# Sheet1.net
KiCad netlist of a schematic drawn in Altium Designer
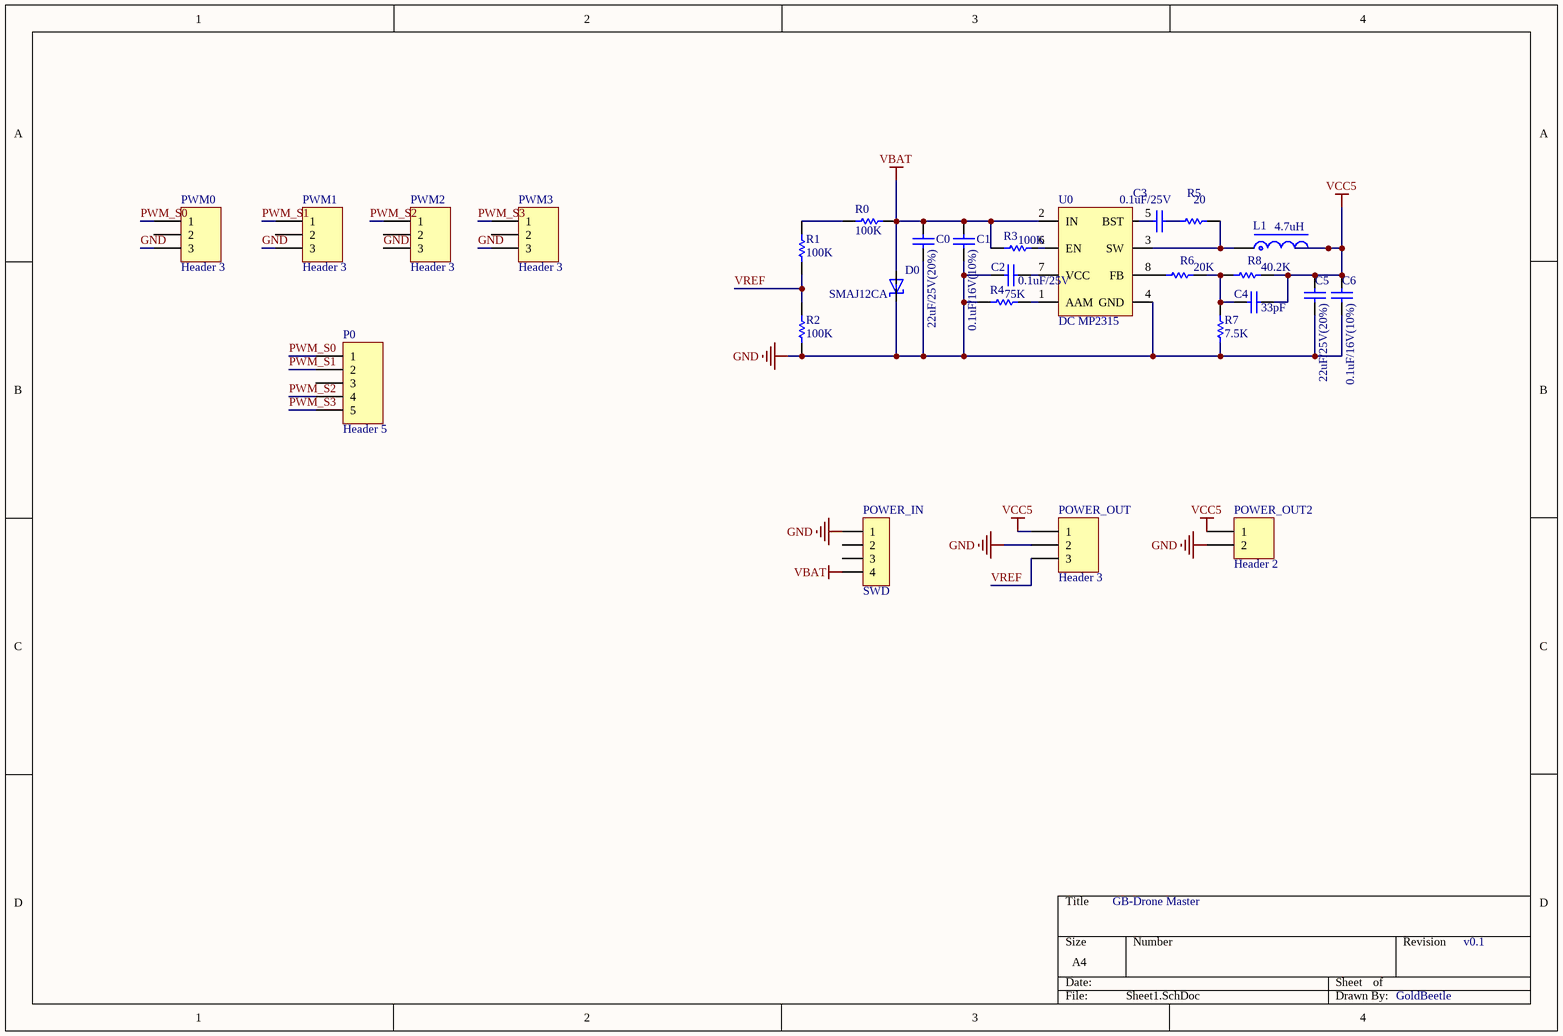
[diagram p0: Sheet1.SchDoc]

(export (version "E")
  (design (tool "Eeschema 10.0.6"))
  (components
    (comp (ref "C0")
      (value "22uF/25V(20%)")
      (footprint "C0805")
      (description "Capacitor")
      (fields (field (name "PUBLISHER") "Altium Limited"))
      (libsource (lib "Miscellaneous Devices") (part "Cap"))
    )
    (comp (ref "C1")
      (value "0.1uF/16V(10%)")
      (footprint "C0805")
      (description "Capacitor")
      (fields (field (name "PUBLISHER") "Altium Limited"))
      (libsource (lib "Miscellaneous Devices") (part "Cap"))
    )
    (comp (ref "C2")
      (value "0.1uF/25V")
      (footprint "C0805")
      (description "Capacitor")
      (fields (field (name "PUBLISHER") "Altium Limited"))
      (libsource (lib "Miscellaneous Devices") (part "Cap"))
    )
    (comp (ref "C3")
      (value "0.1uF/25V")
      (footprint "C0805")
      (description "Capacitor")
      (fields (field (name "PUBLISHER") "Altium Limited"))
      (libsource (lib "Miscellaneous Devices") (part "Cap"))
    )
    (comp (ref "C4")
      (value "33pF")
      (footprint "C0805")
      (description "Capacitor")
      (fields (field (name "PUBLISHER") "Altium Limited"))
      (libsource (lib "Miscellaneous Devices") (part "Cap"))
    )
    (comp (ref "C5")
      (value "22uF/25V(20%)")
      (footprint "C0805")
      (description "Capacitor")
      (fields (field (name "PUBLISHER") "Altium Limited"))
      (libsource (lib "Miscellaneous Devices") (part "Cap"))
    )
    (comp (ref "C6")
      (value "0.1uF/16V(10%)")
      (footprint "C0805")
      (description "Capacitor")
      (fields (field (name "PUBLISHER") "Altium Limited"))
      (libsource (lib "Miscellaneous Devices") (part "Cap"))
    )
    (comp (ref "D0")
      (value "SMAJ12CA")
      (footprint "DO-214AC")
      (description "19.9V Clamp 20.1A Ipp Tvs Diode Surface Mount SMAJ _DO-214AC_")
      (fields (field (name "MF") "Taiwan Semiconductor"))
      (libsource (lib "welkin_lib_v1.0") (part "SMAJ12CA"))
    )
    (comp (ref "L1")
      (value "4.7uH")
      (footprint "INDC6060X300")
      (description "NR功率电感")
      (fields (field (name "版权归属") "源创客"))
      (libsource (lib "welkin_lib_v1.0") (part "L-NR"))
    )
    (comp (ref "P0")
      (value "Header 5")
      (footprint "welkin_pcblib_v1.0:XH2.54-5P")
      (description "Header, 5-Pin")
      (fields (field (name "PUBLISHER") "Altium Limited"))
      (libsource (lib "Miscellaneous Connectors") (part "Header 5"))
    )
    (comp (ref "POWER_IN")
      (value "SWD")
      (footprint "welkin_pcblib_v1.0:XH2.54-4P")
      (description "4P接插件")
      (fields (field (name "版权归属") "源创客"))
      (libsource (lib "welkin_lib_v1.0") (part "Header 4"))
    )
    (comp (ref "POWER_OUT")
      (value "Header 3")
      (footprint "welkin_pcblib_v1.0:XH2.54-3P")
      (description "Header, 3-Pin")
      (fields (field (name "PUBLISHER") "Altium Limited"))
      (libsource (lib "Miscellaneous Connectors") (part "Header 3"))
    )
    (comp (ref "POWER_OUT2")
      (value "Header 2")
      (footprint "welkin_pcblib_v1.0:XH2.54-2P")
      (description "Header, 2-Pin")
      (fields (field (name "PUBLISHER") "Altium Limited"))
      (libsource (lib "Miscellaneous Connectors") (part "Header 2"))
    )
    (comp (ref "PWM0")
      (value "Header 3")
      (footprint "welkin_pcblib_v1.0:XH2.54-3P")
      (description "Header, 3-Pin")
      (fields (field (name "PUBLISHER") "Altium Limited"))
      (libsource (lib "Miscellaneous Connectors") (part "Header 3"))
    )
    (comp (ref "PWM1")
      (value "Header 3")
      (footprint "welkin_pcblib_v1.0:XH2.54-3P")
      (description "Header, 3-Pin")
      (fields (field (name "PUBLISHER") "Altium Limited"))
      (libsource (lib "Miscellaneous Connectors") (part "Header 3"))
    )
    (comp (ref "PWM2")
      (value "Header 3")
      (footprint "welkin_pcblib_v1.0:XH2.54-3P")
      (description "Header, 3-Pin")
      (fields (field (name "PUBLISHER") "Altium Limited"))
      (libsource (lib "Miscellaneous Connectors") (part "Header 3"))
    )
    (comp (ref "PWM3")
      (value "Header 3")
      (footprint "welkin_pcblib_v1.0:XH2.54-3P")
      (description "Header, 3-Pin")
      (fields (field (name "PUBLISHER") "Altium Limited"))
      (libsource (lib "Miscellaneous Connectors") (part "Header 3"))
    )
    (comp (ref "R0")
      (value "100K")
      (footprint "C0805")
      (description "Resistor")
      (fields (field (name "PUBLISHER") "Altium Limited"))
      (libsource (lib "Miscellaneous Devices") (part "Res1"))
    )
    (comp (ref "R1")
      (value "100K")
      (footprint "C0805")
      (description "Resistor")
      (fields (field (name "PUBLISHER") "Altium Limited"))
      (libsource (lib "Miscellaneous Devices") (part "Res1"))
    )
    (comp (ref "R2")
      (value "100K")
      (footprint "C0805")
      (description "Resistor")
      (fields (field (name "PUBLISHER") "Altium Limited"))
      (libsource (lib "Miscellaneous Devices") (part "Res1"))
    )
    (comp (ref "R3")
      (value "100K")
      (footprint "C0805")
      (description "Resistor")
      (fields (field (name "PUBLISHER") "Altium Limited"))
      (libsource (lib "Miscellaneous Devices") (part "Res1"))
    )
    (comp (ref "R4")
      (value "75K")
      (footprint "C0805")
      (description "Resistor")
      (fields (field (name "PUBLISHER") "Altium Limited"))
      (libsource (lib "Miscellaneous Devices") (part "Res1"))
    )
    (comp (ref "R5")
      (value "20")
      (footprint "C0805")
      (description "Resistor")
      (fields (field (name "PUBLISHER") "Altium Limited"))
      (libsource (lib "Miscellaneous Devices") (part "Res1"))
    )
    (comp (ref "R6")
      (value "20K")
      (footprint "C0805")
      (description "Resistor")
      (fields (field (name "PUBLISHER") "Altium Limited"))
      (libsource (lib "Miscellaneous Devices") (part "Res1"))
    )
    (comp (ref "R7")
      (value "7.5K")
      (footprint "C0805")
      (description "Resistor")
      (fields (field (name "PUBLISHER") "Altium Limited"))
      (libsource (lib "Miscellaneous Devices") (part "Res1"))
    )
    (comp (ref "R8")
      (value "40.2K")
      (footprint "C0805")
      (description "Resistor")
      (fields (field (name "PUBLISHER") "Altium Limited"))
      (libsource (lib "Miscellaneous Devices") (part "Res1"))
    )
    (comp (ref "U0")
      (value "DC MP2315")
      (footprint "SOT23-8L")
      (description "DC降压芯片")
      (libsource (lib "welkin_lib_v1.0") (part "DC MP2315"))
    )
  )
  (nets
    (net (code "1") (name "/PWM_S0") (class "Default")
      (node (ref "P0") (pin "1") (pinfunction "1_1") (pintype "passive"))
      (node (ref "PWM0") (pin "1") (pinfunction "1_1") (pintype "passive"))
    )
    (net (code "2") (name "/PWM_S1") (class "Default")
      (node (ref "P0") (pin "2") (pinfunction "2_2") (pintype "passive"))
      (node (ref "PWM1") (pin "1") (pinfunction "1_1") (pintype "passive"))
    )
    (net (code "3") (name "/PWM_S2") (class "Default")
      (node (ref "P0") (pin "4") (pinfunction "4_4") (pintype "passive"))
      (node (ref "PWM2") (pin "1") (pinfunction "1_1") (pintype "passive"))
    )
    (net (code "4") (name "/PWM_S3") (class "Default")
      (node (ref "P0") (pin "5") (pinfunction "5_5") (pintype "passive"))
      (node (ref "PWM3") (pin "1") (pinfunction "1_1") (pintype "passive"))
    )
    (net (code "5") (name "/VREF") (class "Default")
      (node (ref "POWER_OUT") (pin "3") (pinfunction "3_3") (pintype "passive"))
      (node (ref "R1") (pin "2") (pinfunction "2_2") (pintype "passive"))
      (node (ref "R2") (pin "2") (pinfunction "2_2") (pintype "passive"))
    )
    (net (code "6") (name "GND") (class "Default")
      (node (ref "C0") (pin "1") (pinfunction "1_1") (pintype "passive"))
      (node (ref "C1") (pin "1") (pinfunction "1_1") (pintype "passive"))
      (node (ref "C2") (pin "1") (pinfunction "1_1") (pintype "passive"))
      (node (ref "C5") (pin "1") (pinfunction "1_1") (pintype "passive"))
      (node (ref "C6") (pin "1") (pinfunction "1_1") (pintype "passive"))
      (node (ref "D0") (pin "C") (pinfunction "C_C") (pintype "passive"))
      (node (ref "POWER_IN") (pin "1") (pinfunction "1_1") (pintype "passive"))
      (node (ref "POWER_OUT") (pin "2") (pinfunction "2_2") (pintype "passive"))
      (node (ref "POWER_OUT2") (pin "2") (pinfunction "2_2") (pintype "passive"))
      (node (ref "PWM0") (pin "3") (pinfunction "3_3") (pintype "passive"))
      (node (ref "PWM1") (pin "3") (pinfunction "3_3") (pintype "passive"))
      (node (ref "PWM2") (pin "3") (pinfunction "3_3") (pintype "passive"))
      (node (ref "PWM3") (pin "3") (pinfunction "3_3") (pintype "passive"))
      (node (ref "R2") (pin "1") (pinfunction "1_1") (pintype "passive"))
      (node (ref "R4") (pin "1") (pinfunction "1_1") (pintype "passive"))
      (node (ref "R7") (pin "2") (pinfunction "2_2") (pintype "passive"))
      (node (ref "U0") (pin "4") (pinfunction "GND_4") (pintype "passive"))
    )
    (net (code "7") (name "Net-(C3-Pad2)") (class "Default")
      (node (ref "C3") (pin "2") (pinfunction "2_2") (pintype "passive"))
      (node (ref "R5") (pin "1") (pinfunction "1_1") (pintype "passive"))
    )
    (net (code "8") (name "Net-(C4-Pad1)") (class "Default")
      (node (ref "C4") (pin "1") (pinfunction "1_1") (pintype "passive"))
      (node (ref "R6") (pin "2") (pinfunction "2_2") (pintype "passive"))
      (node (ref "R7") (pin "1") (pinfunction "1_1") (pintype "passive"))
      (node (ref "R8") (pin "1") (pinfunction "1_1") (pintype "passive"))
    )
    (net (code "9") (name "Net-(R0-Pad2)") (class "Default")
      (node (ref "R0") (pin "2") (pinfunction "2_2") (pintype "passive"))
      (node (ref "R1") (pin "1") (pinfunction "1_1") (pintype "passive"))
    )
    (net (code "10") (name "Net-(U0-AAM)") (class "Default")
      (node (ref "R4") (pin "2") (pinfunction "2_2") (pintype "passive"))
      (node (ref "U0") (pin "1") (pinfunction "AAM_1") (pintype "passive"))
    )
    (net (code "11") (name "Net-(U0-BST)") (class "Default")
      (node (ref "C3") (pin "1") (pinfunction "1_1") (pintype "passive"))
      (node (ref "U0") (pin "5") (pinfunction "BST_5") (pintype "passive"))
    )
    (net (code "12") (name "Net-(U0-EN)") (class "Default")
      (node (ref "R3") (pin "2") (pinfunction "2_2") (pintype "passive"))
      (node (ref "U0") (pin "6") (pinfunction "EN_6") (pintype "passive"))
    )
    (net (code "13") (name "Net-(U0-FB)") (class "Default")
      (node (ref "R6") (pin "1") (pinfunction "1_1") (pintype "passive"))
      (node (ref "U0") (pin "8") (pinfunction "FB_8") (pintype "passive"))
    )
    (net (code "14") (name "Net-(U0-SW)") (class "Default")
      (node (ref "L1") (pin "1") (pinfunction "1_1") (pintype "passive"))
      (node (ref "R5") (pin "2") (pinfunction "2_2") (pintype "passive"))
      (node (ref "U0") (pin "3") (pinfunction "SW_3") (pintype "passive"))
    )
    (net (code "15") (name "Net-(U0-VCC)") (class "Default")
      (node (ref "C2") (pin "2") (pinfunction "2_2") (pintype "passive"))
      (node (ref "U0") (pin "7") (pinfunction "VCC_7") (pintype "passive"))
    )
    (net (code "16") (name "VBAT") (class "Default")
      (node (ref "C0") (pin "2") (pinfunction "2_2") (pintype "passive"))
      (node (ref "C1") (pin "2") (pinfunction "2_2") (pintype "passive"))
      (node (ref "D0") (pin "A") (pinfunction "A_A") (pintype "passive"))
      (node (ref "POWER_IN") (pin "4") (pinfunction "4_4") (pintype "passive"))
      (node (ref "R0") (pin "1") (pinfunction "1_1") (pintype "passive"))
      (node (ref "R3") (pin "1") (pinfunction "1_1") (pintype "passive"))
      (node (ref "U0") (pin "2") (pinfunction "IN_2") (pintype "passive"))
    )
    (net (code "17") (name "VCC5") (class "Default")
      (node (ref "C4") (pin "2") (pinfunction "2_2") (pintype "passive"))
      (node (ref "C5") (pin "2") (pinfunction "2_2") (pintype "passive"))
      (node (ref "C6") (pin "2") (pinfunction "2_2") (pintype "passive"))
      (node (ref "L1") (pin "2") (pinfunction "2_2") (pintype "passive"))
      (node (ref "POWER_OUT") (pin "1") (pinfunction "1_1") (pintype "passive"))
      (node (ref "POWER_OUT2") (pin "1") (pinfunction "1_1") (pintype "passive"))
      (node (ref "R8") (pin "2") (pinfunction "2_2") (pintype "passive"))
    )
    (net (code "18") (name "unconnected-(P0-Pad3)") (class "Default")
      (node (ref "P0") (pin "3") (pinfunction "3_3") (pintype "passive"))
    )
    (net (code "19") (name "unconnected-(POWER_IN-Pad2)") (class "Default")
      (node (ref "POWER_IN") (pin "2") (pinfunction "2_2") (pintype "passive"))
    )
    (net (code "20") (name "unconnected-(POWER_IN-Pad3)") (class "Default")
      (node (ref "POWER_IN") (pin "3") (pinfunction "3_3") (pintype "passive"))
    )
    (net (code "21") (name "unconnected-(PWM0-Pad2)") (class "Default")
      (node (ref "PWM0") (pin "2") (pinfunction "2_2") (pintype "passive"))
    )
    (net (code "22") (name "unconnected-(PWM1-Pad2)") (class "Default")
      (node (ref "PWM1") (pin "2") (pinfunction "2_2") (pintype "passive"))
    )
    (net (code "23") (name "unconnected-(PWM2-Pad2)") (class "Default")
      (node (ref "PWM2") (pin "2") (pinfunction "2_2") (pintype "passive"))
    )
    (net (code "24") (name "unconnected-(PWM3-Pad2)") (class "Default")
      (node (ref "PWM3") (pin "2") (pinfunction "2_2") (pintype "passive"))
    )
  )
)
